# Relay_Board_V5.net
KiCad netlist of a schematic drawn in EAGLE
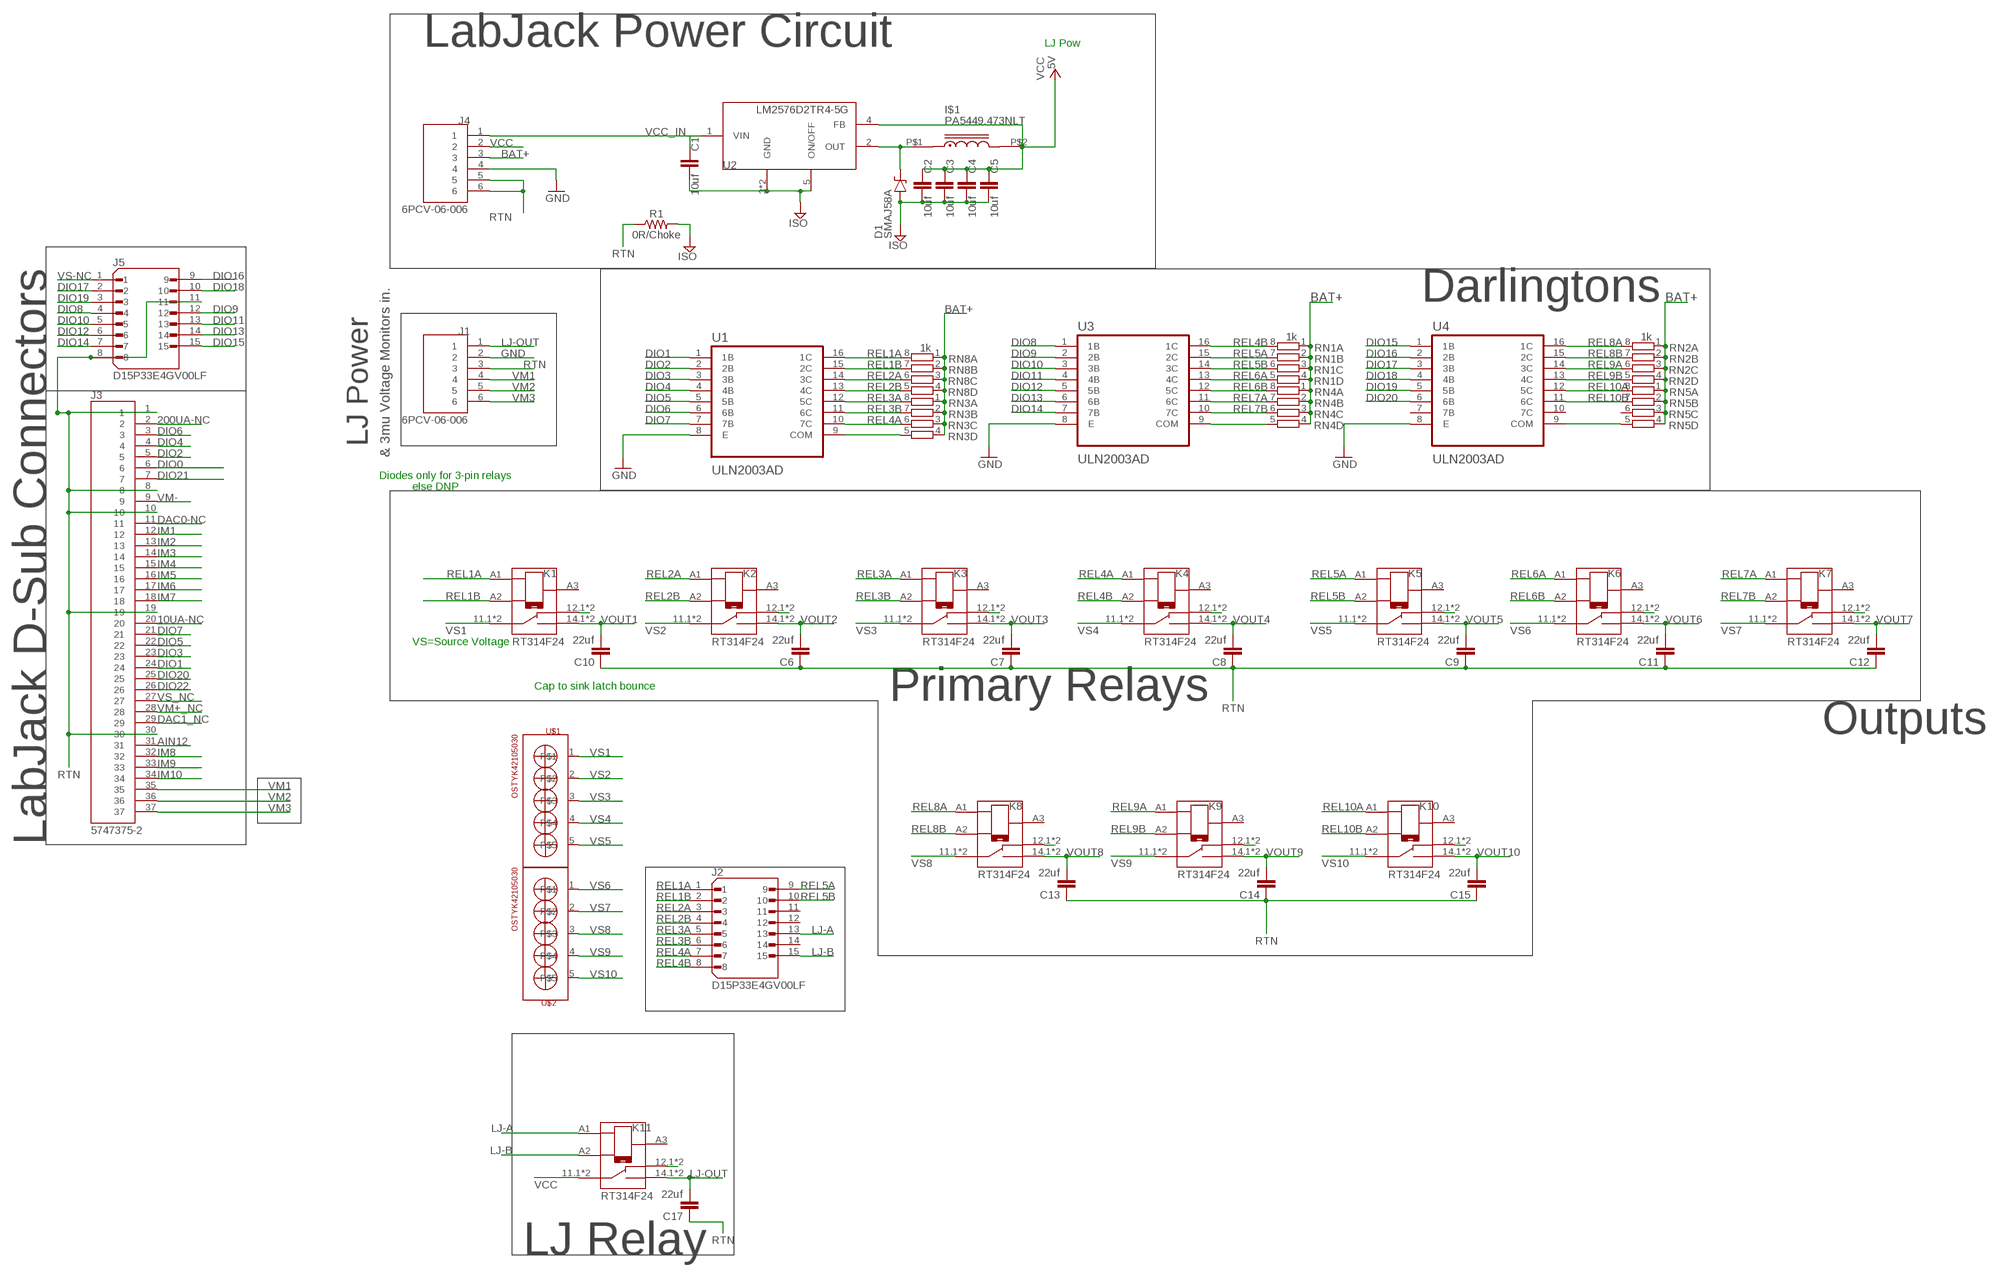
[diagram p0: schematic, sheet 1, part 1 of 2]
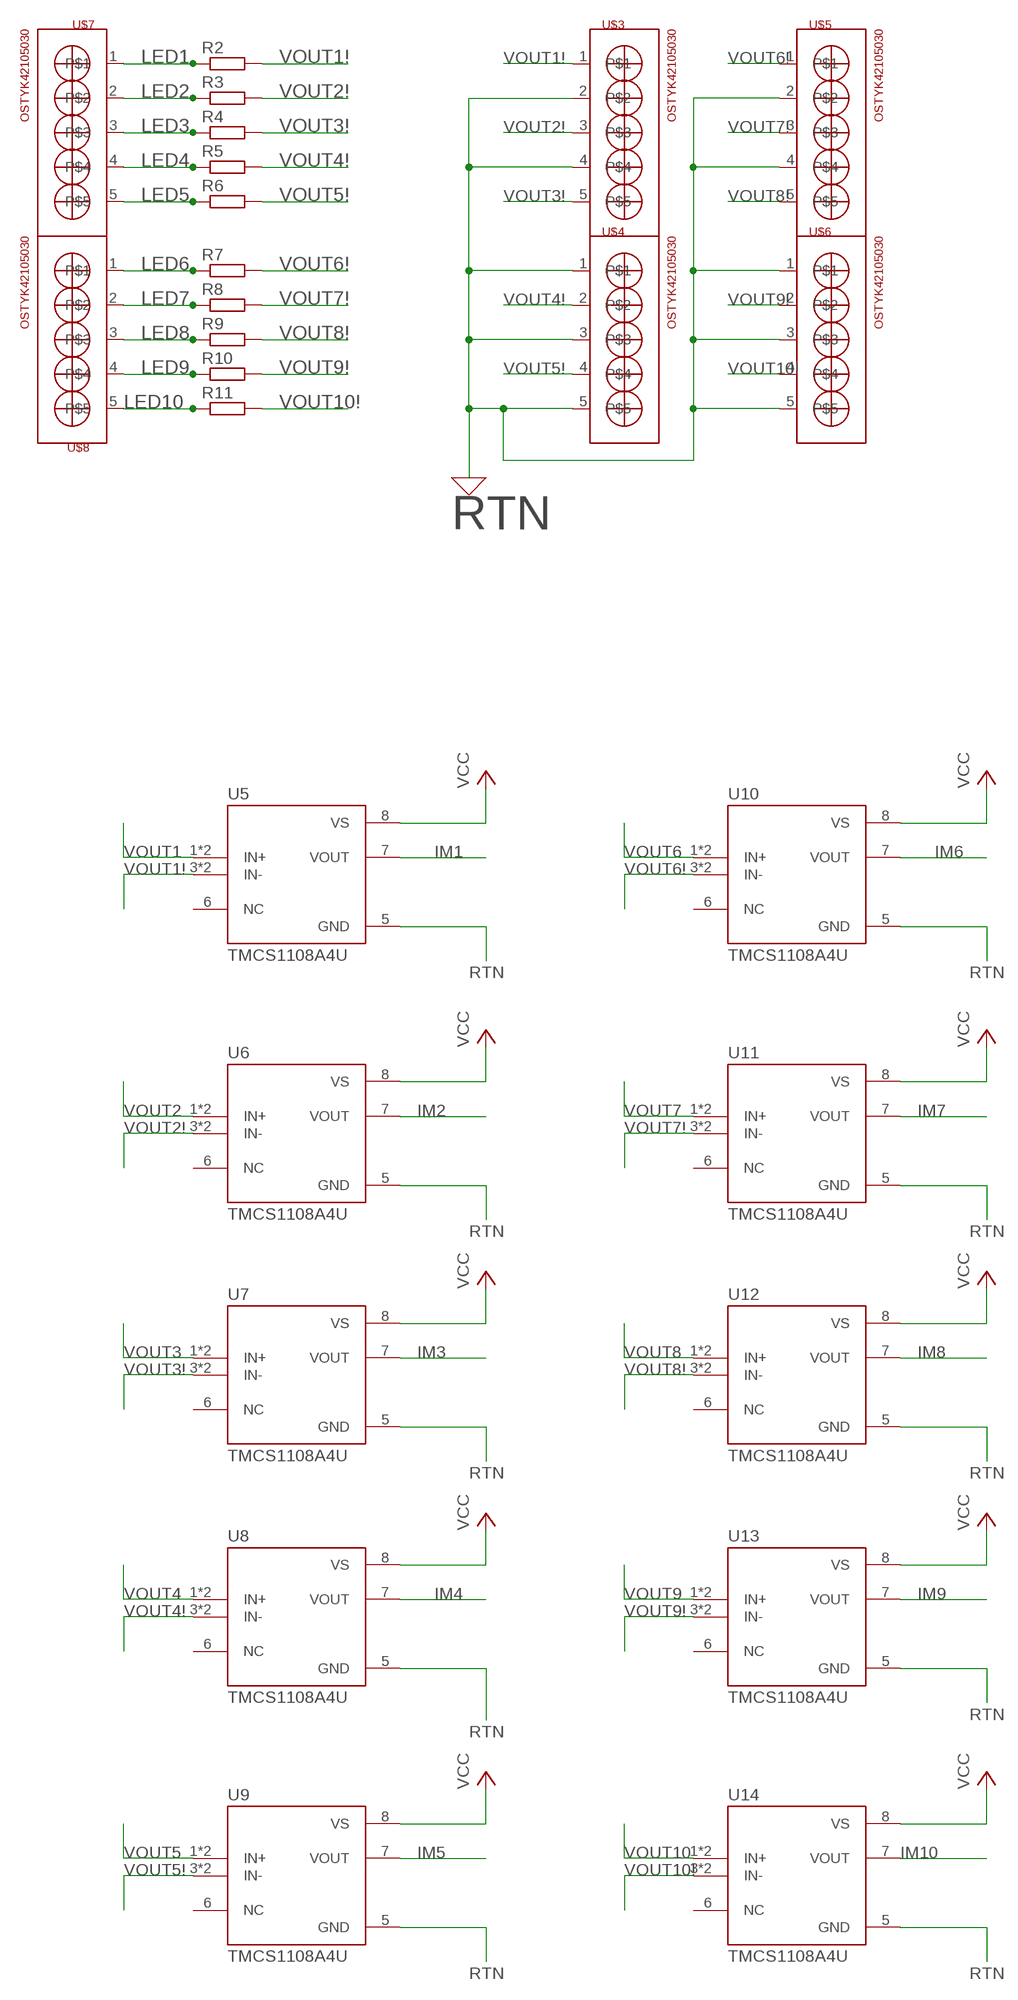
[diagram p1: schematic, sheet 1, part 2 of 2]

(export (version "E")
  (design (tool "Eeschema 10.0.6"))
  (components
    (comp (ref "C1")
      (value "10uf")
      (footprint "eagle-import:0805")
      (libsource (lib "eagle-import") (part "39NF-0805-50V-10%"))
    )
    (comp (ref "C2")
      (value "10uf")
      (footprint "eagle-import:0805")
      (libsource (lib "eagle-import") (part "39NF-0805-50V-10%"))
    )
    (comp (ref "C3")
      (value "10uf")
      (footprint "eagle-import:0805")
      (libsource (lib "eagle-import") (part "39NF-0805-50V-10%"))
    )
    (comp (ref "C4")
      (value "10uf")
      (footprint "eagle-import:0805")
      (libsource (lib "eagle-import") (part "39NF-0805-50V-10%"))
    )
    (comp (ref "C5")
      (value "10uf")
      (footprint "eagle-import:0805")
      (libsource (lib "eagle-import") (part "39NF-0805-50V-10%"))
    )
    (comp (ref "C6")
      (value "22uf")
      (footprint "eagle-import:0603")
      (libsource (lib "eagle-import") (part "5.6NF/5600PF_0603_50V_5%"))
    )
    (comp (ref "C7")
      (value "22uf")
      (footprint "eagle-import:0603")
      (libsource (lib "eagle-import") (part "5.6NF/5600PF_0603_50V_5%"))
    )
    (comp (ref "C8")
      (value "22uf")
      (footprint "eagle-import:0603")
      (libsource (lib "eagle-import") (part "5.6NF/5600PF_0603_50V_5%"))
    )
    (comp (ref "C9")
      (value "22uf")
      (footprint "eagle-import:0603")
      (libsource (lib "eagle-import") (part "5.6NF/5600PF_0603_50V_5%"))
    )
    (comp (ref "C10")
      (value "22uf")
      (footprint "eagle-import:0603")
      (libsource (lib "eagle-import") (part "5.6NF/5600PF_0603_50V_5%"))
    )
    (comp (ref "C11")
      (value "22uf")
      (footprint "eagle-import:0603")
      (libsource (lib "eagle-import") (part "5.6NF/5600PF_0603_50V_5%"))
    )
    (comp (ref "C12")
      (value "22uf")
      (footprint "eagle-import:0603")
      (libsource (lib "eagle-import") (part "5.6NF/5600PF_0603_50V_5%"))
    )
    (comp (ref "C13")
      (value "22uf")
      (footprint "eagle-import:0603")
      (libsource (lib "eagle-import") (part "5.6NF/5600PF_0603_50V_5%"))
    )
    (comp (ref "C14")
      (value "22uf")
      (footprint "eagle-import:0603")
      (libsource (lib "eagle-import") (part "5.6NF/5600PF_0603_50V_5%"))
    )
    (comp (ref "C15")
      (value "22uf")
      (footprint "eagle-import:0603")
      (libsource (lib "eagle-import") (part "5.6NF/5600PF_0603_50V_5%"))
    )
    (comp (ref "C17")
      (value "22uf")
      (footprint "eagle-import:0603")
      (libsource (lib "eagle-import") (part "5.6NF/5600PF_0603_50V_5%"))
    )
    (comp (ref "D1")
      (value "SMAJ58A")
      (footprint "eagle-import:SMA")
      (fields (field (name "MF") "Littelfuse Inc."))
      (libsource (lib "eagle-import") (part "SMAJ58A"))
    )
    (comp (ref "I$1")
      (value "PA5449.473NLT")
      (footprint "eagle-import:IND_TYS4020470M-10")
      (libsource (lib "eagle-import") (part "PULSE_ELECTRONICS_INDUCTOR"))
    )
    (comp (ref "J1")
      (value "6PCV-06-006")
      (footprint "eagle-import:TE_9-1437652-5")
      (fields (field (name "COMMENT") "9-1437652-5") (field (name "MF") "TE Connectivity"))
      (libsource (lib "eagle-import") (part "6PCV-06-006"))
    )
    (comp (ref "J2")
      (value "D15P33E4GV00LF")
      (footprint "eagle-import:AMPHENOL_D15P33E4GV00LF")
      (fields (field (name "MF") "Amphenol ICC"))
      (libsource (lib "eagle-import") (part "D15P33E4GV00LF"))
    )
    (comp (ref "J3")
      (value "5747375-2")
      (footprint "eagle-import:TE_5747375-2")
      (fields (field (name "DIGI-KEY_PART_NUMBER") "A34071-ND") (field (name "MF") "TE Connectivity"))
      (libsource (lib "eagle-import") (part "5747375-2"))
    )
    (comp (ref "J4")
      (value "6PCV-06-006")
      (footprint "eagle-import:TE_9-1437652-5")
      (fields (field (name "COMMENT") "9-1437652-5") (field (name "MF") "TE Connectivity"))
      (libsource (lib "eagle-import") (part "6PCV-06-006"))
    )
    (comp (ref "J5")
      (value "D15P33E4GV00LF")
      (footprint "eagle-import:AMPHENOL_D15P33E4GV00LF")
      (fields (field (name "MF") "Amphenol ICC"))
      (libsource (lib "eagle-import") (part "D15P33E4GV00LF"))
    )
    (comp (ref "K1")
      (value "RT314F24")
      (footprint "eagle-import:TE_8-1393239-8")
      (fields (field (name "COMMENT") "8-1393239-8") (field (name "MF") "TE Connectivity"))
      (libsource (lib "eagle-import") (part "8-1393239-8"))
    )
    (comp (ref "K2")
      (value "RT314F24")
      (footprint "eagle-import:TE_8-1393239-8")
      (fields (field (name "COMMENT") "8-1393239-8") (field (name "MF") "TE Connectivity"))
      (libsource (lib "eagle-import") (part "8-1393239-8"))
    )
    (comp (ref "K3")
      (value "RT314F24")
      (footprint "eagle-import:TE_8-1393239-8")
      (fields (field (name "COMMENT") "8-1393239-8") (field (name "MF") "TE Connectivity"))
      (libsource (lib "eagle-import") (part "8-1393239-8"))
    )
    (comp (ref "K4")
      (value "RT314F24")
      (footprint "eagle-import:TE_8-1393239-8")
      (fields (field (name "COMMENT") "8-1393239-8") (field (name "MF") "TE Connectivity"))
      (libsource (lib "eagle-import") (part "8-1393239-8"))
    )
    (comp (ref "K5")
      (value "RT314F24")
      (footprint "eagle-import:TE_8-1393239-8")
      (fields (field (name "COMMENT") "8-1393239-8") (field (name "MF") "TE Connectivity"))
      (libsource (lib "eagle-import") (part "8-1393239-8"))
    )
    (comp (ref "K6")
      (value "RT314F24")
      (footprint "eagle-import:TE_8-1393239-8")
      (fields (field (name "COMMENT") "8-1393239-8") (field (name "MF") "TE Connectivity"))
      (libsource (lib "eagle-import") (part "8-1393239-8"))
    )
    (comp (ref "K7")
      (value "RT314F24")
      (footprint "eagle-import:TE_8-1393239-8")
      (fields (field (name "COMMENT") "8-1393239-8") (field (name "MF") "TE Connectivity"))
      (libsource (lib "eagle-import") (part "8-1393239-8"))
    )
    (comp (ref "K8")
      (value "RT314F24")
      (footprint "eagle-import:TE_8-1393239-8")
      (fields (field (name "COMMENT") "8-1393239-8") (field (name "MF") "TE Connectivity"))
      (libsource (lib "eagle-import") (part "8-1393239-8"))
    )
    (comp (ref "K9")
      (value "RT314F24")
      (footprint "eagle-import:TE_8-1393239-8")
      (fields (field (name "COMMENT") "8-1393239-8") (field (name "MF") "TE Connectivity"))
      (libsource (lib "eagle-import") (part "8-1393239-8"))
    )
    (comp (ref "K10")
      (value "RT314F24")
      (footprint "eagle-import:TE_8-1393239-8")
      (fields (field (name "COMMENT") "8-1393239-8") (field (name "MF") "TE Connectivity"))
      (libsource (lib "eagle-import") (part "8-1393239-8"))
    )
    (comp (ref "K11")
      (value "RT314F24")
      (footprint "eagle-import:TE_8-1393239-8")
      (fields (field (name "COMMENT") "8-1393239-8") (field (name "MF") "TE Connectivity"))
      (libsource (lib "eagle-import") (part "8-1393239-8"))
    )
    (comp (ref "R1")
      (value "0R/Choke")
      (footprint "eagle-import:0603")
      (libsource (lib "eagle-import") (part "1.8MOHM"))
    )
    (comp (ref "R2")
      (value "R-EU_0204/7")
      (footprint "eagle-import:0204_7")
      (libsource (lib "eagle-import") (part "R-EU_0204/7"))
    )
    (comp (ref "R3")
      (value "R-EU_0204/7")
      (footprint "eagle-import:0204_7")
      (libsource (lib "eagle-import") (part "R-EU_0204/7"))
    )
    (comp (ref "R4")
      (value "R-EU_0204/7")
      (footprint "eagle-import:0204_7")
      (libsource (lib "eagle-import") (part "R-EU_0204/7"))
    )
    (comp (ref "R5")
      (value "R-EU_0204/7")
      (footprint "eagle-import:0204_7")
      (libsource (lib "eagle-import") (part "R-EU_0204/7"))
    )
    (comp (ref "R6")
      (value "R-EU_0204/7")
      (footprint "eagle-import:0204_7")
      (libsource (lib "eagle-import") (part "R-EU_0204/7"))
    )
    (comp (ref "R7")
      (value "R-EU_0204/7")
      (footprint "eagle-import:0204_7")
      (libsource (lib "eagle-import") (part "R-EU_0204/7"))
    )
    (comp (ref "R8")
      (value "R-EU_0204/7")
      (footprint "eagle-import:0204_7")
      (libsource (lib "eagle-import") (part "R-EU_0204/7"))
    )
    (comp (ref "R9")
      (value "R-EU_0204/7")
      (footprint "eagle-import:0204_7")
      (libsource (lib "eagle-import") (part "R-EU_0204/7"))
    )
    (comp (ref "R10")
      (value "R-EU_0204/7")
      (footprint "eagle-import:0204_7")
      (libsource (lib "eagle-import") (part "R-EU_0204/7"))
    )
    (comp (ref "R11")
      (value "R-EU_0204/7")
      (footprint "eagle-import:0204_7")
      (libsource (lib "eagle-import") (part "R-EU_0204/7"))
    )
    (comp (ref "RN1")
      (value "1k")
      (footprint "eagle-import:CAY16")
      (fields (field (name "PART_NUMBER") "064R_10K_/_CAY16-103J4LF"))
      (libsource (lib "eagle-import") (part "0016_064R_10K_/_CAY16-103J4LF"))
    )
    (comp (ref "RN2")
      (value "1k")
      (footprint "eagle-import:CAY16")
      (fields (field (name "PART_NUMBER") "064R_10K_/_CAY16-103J4LF"))
      (libsource (lib "eagle-import") (part "0016_064R_10K_/_CAY16-103J4LF"))
    )
    (comp (ref "RN3")
      (value "1k")
      (footprint "eagle-import:CAY16")
      (fields (field (name "PART_NUMBER") "064R_10K_/_CAY16-103J4LF"))
      (libsource (lib "eagle-import") (part "0016_064R_10K_/_CAY16-103J4LF"))
    )
    (comp (ref "RN4")
      (value "1k")
      (footprint "eagle-import:CAY16")
      (fields (field (name "PART_NUMBER") "064R_10K_/_CAY16-103J4LF"))
      (libsource (lib "eagle-import") (part "0016_064R_10K_/_CAY16-103J4LF"))
    )
    (comp (ref "RN5")
      (value "1k")
      (footprint "eagle-import:CAY16")
      (fields (field (name "PART_NUMBER") "064R_10K_/_CAY16-103J4LF"))
      (libsource (lib "eagle-import") (part "0016_064R_10K_/_CAY16-103J4LF"))
    )
    (comp (ref "RN8")
      (value "1k")
      (footprint "eagle-import:CAY16")
      (fields (field (name "PART_NUMBER") "064R_10K_/_CAY16-103J4LF"))
      (libsource (lib "eagle-import") (part "0016_064R_10K_/_CAY16-103J4LF"))
    )
    (comp (ref "U$1")
      (value "OSTYK42105030")
      (footprint "eagle-import:OSTYK42105030")
      (fields (field (name "MF") "On Shore Technology Inc."))
      (libsource (lib "eagle-import") (part "OSTYK42105030"))
    )
    (comp (ref "U$2")
      (value "OSTYK42105030")
      (footprint "eagle-import:OSTYK42105030")
      (fields (field (name "MF") "On Shore Technology Inc."))
      (libsource (lib "eagle-import") (part "OSTYK42105030"))
    )
    (comp (ref "U$3")
      (value "OSTYK42105030")
      (footprint "eagle-import:OSTYK42105030")
      (fields (field (name "MF") "On Shore Technology Inc."))
      (libsource (lib "eagle-import") (part "OSTYK42105030"))
    )
    (comp (ref "U$4")
      (value "OSTYK42105030")
      (footprint "eagle-import:OSTYK42105030")
      (fields (field (name "MF") "On Shore Technology Inc."))
      (libsource (lib "eagle-import") (part "OSTYK42105030"))
    )
    (comp (ref "U$5")
      (value "OSTYK42105030")
      (footprint "eagle-import:OSTYK42105030")
      (fields (field (name "MF") "On Shore Technology Inc."))
      (libsource (lib "eagle-import") (part "OSTYK42105030"))
    )
    (comp (ref "U$6")
      (value "OSTYK42105030")
      (footprint "eagle-import:OSTYK42105030")
      (fields (field (name "MF") "On Shore Technology Inc."))
      (libsource (lib "eagle-import") (part "OSTYK42105030"))
    )
    (comp (ref "U$7")
      (value "OSTYK42105030")
      (footprint "eagle-import:OSTYK42105030")
      (fields (field (name "MF") "On Shore Technology Inc."))
      (libsource (lib "eagle-import") (part "OSTYK42105030"))
    )
    (comp (ref "U$8")
      (value "OSTYK42105030")
      (footprint "eagle-import:OSTYK42105030")
      (fields (field (name "MF") "On Shore Technology Inc."))
      (libsource (lib "eagle-import") (part "OSTYK42105030"))
    )
    (comp (ref "U1")
      (value "ULN2003AD")
      (footprint "eagle-import:SOIC127P600X175-16N")
      (fields (field (name "MF") "Texas Instruments"))
      (libsource (lib "eagle-import") (part "ULN2003AD"))
    )
    (comp (ref "U2")
      (value "LM2576D2TR4-5G")
      (footprint "eagle-import:D2PAK-5")
      (fields (field (name "MF") "ON Semiconductor"))
      (libsource (lib "eagle-import") (part "LM2576D2TR4-5G"))
    )
    (comp (ref "U3")
      (value "ULN2003AD")
      (footprint "eagle-import:SOIC127P600X175-16N")
      (fields (field (name "MF") "Texas Instruments"))
      (libsource (lib "eagle-import") (part "ULN2003AD"))
    )
    (comp (ref "U4")
      (value "ULN2003AD")
      (footprint "eagle-import:SOIC127P600X175-16N")
      (fields (field (name "MF") "Texas Instruments"))
      (libsource (lib "eagle-import") (part "ULN2003AD"))
    )
    (comp (ref "U5")
      (value "TMCS1108A4U")
      (footprint "eagle-import:SOIC127P599X175-8N")
      (fields (field (name "MF") "Texas Instruments") (field (name "MP") "TMCS1108A3UQDRQ1"))
      (libsource (lib "eagle-import") (part "TMCS1108A3UQDRQ1"))
    )
    (comp (ref "U6")
      (value "TMCS1108A4U")
      (footprint "eagle-import:SOIC127P599X175-8N")
      (fields (field (name "MF") "Texas Instruments") (field (name "MP") "TMCS1108A3UQDRQ1"))
      (libsource (lib "eagle-import") (part "TMCS1108A3UQDRQ1"))
    )
    (comp (ref "U7")
      (value "TMCS1108A4U")
      (footprint "eagle-import:SOIC127P599X175-8N")
      (fields (field (name "MF") "Texas Instruments") (field (name "MP") "TMCS1108A3UQDRQ1"))
      (libsource (lib "eagle-import") (part "TMCS1108A3UQDRQ1"))
    )
    (comp (ref "U8")
      (value "TMCS1108A4U")
      (footprint "eagle-import:SOIC127P599X175-8N")
      (fields (field (name "MF") "Texas Instruments") (field (name "MP") "TMCS1108A3UQDRQ1"))
      (libsource (lib "eagle-import") (part "TMCS1108A3UQDRQ1"))
    )
    (comp (ref "U9")
      (value "TMCS1108A4U")
      (footprint "eagle-import:SOIC127P599X175-8N")
      (fields (field (name "MF") "Texas Instruments") (field (name "MP") "TMCS1108A3UQDRQ1"))
      (libsource (lib "eagle-import") (part "TMCS1108A3UQDRQ1"))
    )
    (comp (ref "U10")
      (value "TMCS1108A4U")
      (footprint "eagle-import:SOIC127P599X175-8N")
      (fields (field (name "MF") "Texas Instruments") (field (name "MP") "TMCS1108A3UQDRQ1"))
      (libsource (lib "eagle-import") (part "TMCS1108A3UQDRQ1"))
    )
    (comp (ref "U11")
      (value "TMCS1108A4U")
      (footprint "eagle-import:SOIC127P599X175-8N")
      (fields (field (name "MF") "Texas Instruments") (field (name "MP") "TMCS1108A3UQDRQ1"))
      (libsource (lib "eagle-import") (part "TMCS1108A3UQDRQ1"))
    )
    (comp (ref "U12")
      (value "TMCS1108A4U")
      (footprint "eagle-import:SOIC127P599X175-8N")
      (fields (field (name "MF") "Texas Instruments") (field (name "MP") "TMCS1108A3UQDRQ1"))
      (libsource (lib "eagle-import") (part "TMCS1108A3UQDRQ1"))
    )
    (comp (ref "U13")
      (value "TMCS1108A4U")
      (footprint "eagle-import:SOIC127P599X175-8N")
      (fields (field (name "MF") "Texas Instruments") (field (name "MP") "TMCS1108A3UQDRQ1"))
      (libsource (lib "eagle-import") (part "TMCS1108A3UQDRQ1"))
    )
    (comp (ref "U14")
      (value "TMCS1108A4U")
      (footprint "eagle-import:SOIC127P599X175-8N")
      (fields (field (name "MF") "Texas Instruments") (field (name "MP") "TMCS1108A3UQDRQ1"))
      (libsource (lib "eagle-import") (part "TMCS1108A3UQDRQ1"))
    )
  )
  (nets
    (net (code "1") (name "/10UA-NC") (class "Default")
      (node (ref "J3") (pin "20") (pinfunction "20_20") (pintype "passive"))
    )
    (net (code "2") (name "/200UA-NC") (class "Default")
      (node (ref "J3") (pin "2") (pinfunction "2_2") (pintype "passive"))
    )
    (net (code "3") (name "/AIN12") (class "Default")
      (node (ref "J3") (pin "31") (pinfunction "31_31") (pintype "passive"))
    )
    (net (code "4") (name "/BAT+") (class "Default")
      (node (ref "J4") (pin "3") (pinfunction "3_3") (pintype "passive"))
      (node (ref "RN1") (pin "1") (pinfunction "1_1") (pintype "passive"))
      (node (ref "RN1") (pin "2") (pinfunction "1_2") (pintype "passive"))
      (node (ref "RN1") (pin "3") (pinfunction "1_3") (pintype "passive"))
      (node (ref "RN1") (pin "4") (pinfunction "1_4") (pintype "passive"))
      (node (ref "RN2") (pin "1") (pinfunction "1_1") (pintype "passive"))
      (node (ref "RN2") (pin "2") (pinfunction "1_2") (pintype "passive"))
      (node (ref "RN2") (pin "3") (pinfunction "1_3") (pintype "passive"))
      (node (ref "RN2") (pin "4") (pinfunction "1_4") (pintype "passive"))
      (node (ref "RN3") (pin "1") (pinfunction "1_1") (pintype "passive"))
      (node (ref "RN3") (pin "2") (pinfunction "1_2") (pintype "passive"))
      (node (ref "RN3") (pin "3") (pinfunction "1_3") (pintype "passive"))
      (node (ref "RN3") (pin "4") (pinfunction "1_4") (pintype "passive"))
      (node (ref "RN4") (pin "1") (pinfunction "1_1") (pintype "passive"))
      (node (ref "RN4") (pin "2") (pinfunction "1_2") (pintype "passive"))
      (node (ref "RN4") (pin "3") (pinfunction "1_3") (pintype "passive"))
      (node (ref "RN4") (pin "4") (pinfunction "1_4") (pintype "passive"))
      (node (ref "RN5") (pin "1") (pinfunction "1_1") (pintype "passive"))
      (node (ref "RN5") (pin "2") (pinfunction "1_2") (pintype "passive"))
      (node (ref "RN5") (pin "3") (pinfunction "1_3") (pintype "passive"))
      (node (ref "RN5") (pin "4") (pinfunction "1_4") (pintype "passive"))
      (node (ref "RN8") (pin "1") (pinfunction "1_1") (pintype "passive"))
      (node (ref "RN8") (pin "2") (pinfunction "1_2") (pintype "passive"))
      (node (ref "RN8") (pin "3") (pinfunction "1_3") (pintype "passive"))
      (node (ref "RN8") (pin "4") (pinfunction "1_4") (pintype "passive"))
    )
    (net (code "5") (name "/DAC0-NC") (class "Default")
      (node (ref "J3") (pin "11") (pinfunction "11_11") (pintype "passive"))
    )
    (net (code "6") (name "/DAC1_NC") (class "Default")
      (node (ref "J3") (pin "29") (pinfunction "29_29") (pintype "passive"))
    )
    (net (code "7") (name "/DIO0") (class "Default")
      (node (ref "J3") (pin "6") (pinfunction "6_6") (pintype "passive"))
    )
    (net (code "8") (name "/DIO1") (class "Default")
      (node (ref "J3") (pin "24") (pinfunction "24_24") (pintype "passive"))
      (node (ref "U1") (pin "1") (pinfunction "1B_1") (pintype "input"))
    )
    (net (code "9") (name "/DIO2") (class "Default")
      (node (ref "J3") (pin "5") (pinfunction "5_5") (pintype "passive"))
      (node (ref "U1") (pin "2") (pinfunction "2B_2") (pintype "input"))
    )
    (net (code "10") (name "/DIO3") (class "Default")
      (node (ref "J3") (pin "23") (pinfunction "23_23") (pintype "passive"))
      (node (ref "U1") (pin "3") (pinfunction "3B_3") (pintype "input"))
    )
    (net (code "11") (name "/DIO4") (class "Default")
      (node (ref "J3") (pin "4") (pinfunction "4_4") (pintype "passive"))
      (node (ref "U1") (pin "4") (pinfunction "4B_4") (pintype "input"))
    )
    (net (code "12") (name "/DIO5") (class "Default")
      (node (ref "J3") (pin "22") (pinfunction "22_22") (pintype "passive"))
      (node (ref "U1") (pin "5") (pinfunction "5B_5") (pintype "input"))
    )
    (net (code "13") (name "/DIO6") (class "Default")
      (node (ref "J3") (pin "3") (pinfunction "3_3") (pintype "passive"))
      (node (ref "U1") (pin "6") (pinfunction "6B_6") (pintype "input"))
    )
    (net (code "14") (name "/DIO7") (class "Default")
      (node (ref "J3") (pin "21") (pinfunction "21_21") (pintype "passive"))
      (node (ref "U1") (pin "7") (pinfunction "7B_7") (pintype "input"))
    )
    (net (code "15") (name "/DIO8") (class "Default")
      (node (ref "J5") (pin "4") (pinfunction "4_4") (pintype "passive"))
      (node (ref "U3") (pin "1") (pinfunction "1B_1") (pintype "input"))
    )
    (net (code "16") (name "/DIO9") (class "Default")
      (node (ref "J5") (pin "12") (pinfunction "12_12") (pintype "passive"))
      (node (ref "U3") (pin "2") (pinfunction "2B_2") (pintype "input"))
    )
    (net (code "17") (name "/DIO10") (class "Default")
      (node (ref "J5") (pin "5") (pinfunction "5_5") (pintype "passive"))
      (node (ref "U3") (pin "3") (pinfunction "3B_3") (pintype "input"))
    )
    (net (code "18") (name "/DIO11") (class "Default")
      (node (ref "J5") (pin "13") (pinfunction "13_13") (pintype "passive"))
      (node (ref "U3") (pin "4") (pinfunction "4B_4") (pintype "input"))
    )
    (net (code "19") (name "/DIO12") (class "Default")
      (node (ref "J5") (pin "6") (pinfunction "6_6") (pintype "passive"))
      (node (ref "U3") (pin "5") (pinfunction "5B_5") (pintype "input"))
    )
    (net (code "20") (name "/DIO13") (class "Default")
      (node (ref "J5") (pin "14") (pinfunction "14_14") (pintype "passive"))
      (node (ref "U3") (pin "6") (pinfunction "6B_6") (pintype "input"))
    )
    (net (code "21") (name "/DIO14") (class "Default")
      (node (ref "J5") (pin "7") (pinfunction "7_7") (pintype "passive"))
      (node (ref "U3") (pin "7") (pinfunction "7B_7") (pintype "input"))
    )
    (net (code "22") (name "/DIO15") (class "Default")
      (node (ref "J5") (pin "15") (pinfunction "15_15") (pintype "passive"))
      (node (ref "U4") (pin "1") (pinfunction "1B_1") (pintype "input"))
    )
    (net (code "23") (name "/DIO16") (class "Default")
      (node (ref "J5") (pin "9") (pinfunction "9_9") (pintype "passive"))
      (node (ref "U4") (pin "2") (pinfunction "2B_2") (pintype "input"))
    )
    (net (code "24") (name "/DIO17") (class "Default")
      (node (ref "J5") (pin "2") (pinfunction "2_2") (pintype "passive"))
      (node (ref "U4") (pin "3") (pinfunction "3B_3") (pintype "input"))
    )
    (net (code "25") (name "/DIO18") (class "Default")
      (node (ref "J5") (pin "10") (pinfunction "10_10") (pintype "passive"))
      (node (ref "U4") (pin "4") (pinfunction "4B_4") (pintype "input"))
    )
    (net (code "26") (name "/DIO19") (class "Default")
      (node (ref "J5") (pin "3") (pinfunction "3_3") (pintype "passive"))
      (node (ref "U4") (pin "5") (pinfunction "5B_5") (pintype "input"))
    )
    (net (code "27") (name "/DIO20") (class "Default")
      (node (ref "J3") (pin "25") (pinfunction "25_25") (pintype "passive"))
      (node (ref "U4") (pin "6") (pinfunction "6B_6") (pintype "input"))
    )
    (net (code "28") (name "/DIO21") (class "Default")
      (node (ref "J3") (pin "7") (pinfunction "7_7") (pintype "passive"))
    )
    (net (code "29") (name "/DIO22") (class "Default")
      (node (ref "J3") (pin "26") (pinfunction "26_26") (pintype "passive"))
    )
    (net (code "30") (name "/IM1") (class "Default")
      (node (ref "J3") (pin "12") (pinfunction "12_12") (pintype "passive"))
      (node (ref "U5") (pin "7") (pinfunction "VOUT_7") (pintype "output"))
    )
    (net (code "31") (name "/IM2") (class "Default")
      (node (ref "J3") (pin "13") (pinfunction "13_13") (pintype "passive"))
      (node (ref "U6") (pin "7") (pinfunction "VOUT_7") (pintype "output"))
    )
    (net (code "32") (name "/IM3") (class "Default")
      (node (ref "J3") (pin "14") (pinfunction "14_14") (pintype "passive"))
      (node (ref "U7") (pin "7") (pinfunction "VOUT_7") (pintype "output"))
    )
    (net (code "33") (name "/IM4") (class "Default")
      (node (ref "J3") (pin "15") (pinfunction "15_15") (pintype "passive"))
      (node (ref "U8") (pin "7") (pinfunction "VOUT_7") (pintype "output"))
    )
    (net (code "34") (name "/IM5") (class "Default")
      (node (ref "J3") (pin "16") (pinfunction "16_16") (pintype "passive"))
      (node (ref "U9") (pin "7") (pinfunction "VOUT_7") (pintype "output"))
    )
    (net (code "35") (name "/IM6") (class "Default")
      (node (ref "J3") (pin "17") (pinfunction "17_17") (pintype "passive"))
      (node (ref "U10") (pin "7") (pinfunction "VOUT_7") (pintype "output"))
    )
    (net (code "36") (name "/IM7") (class "Default")
      (node (ref "J3") (pin "18") (pinfunction "18_18") (pintype "passive"))
      (node (ref "U11") (pin "7") (pinfunction "VOUT_7") (pintype "output"))
    )
    (net (code "37") (name "/IM8") (class "Default")
      (node (ref "J3") (pin "32") (pinfunction "32_32") (pintype "passive"))
      (node (ref "U12") (pin "7") (pinfunction "VOUT_7") (pintype "output"))
    )
    (net (code "38") (name "/IM9") (class "Default")
      (node (ref "J3") (pin "33") (pinfunction "33_33") (pintype "passive"))
      (node (ref "U13") (pin "7") (pinfunction "VOUT_7") (pintype "output"))
    )
    (net (code "39") (name "/IM10") (class "Default")
      (node (ref "J3") (pin "34") (pinfunction "34_34") (pintype "passive"))
      (node (ref "U14") (pin "7") (pinfunction "VOUT_7") (pintype "output"))
    )
    (net (code "40") (name "/LED1") (class "Default")
      (node (ref "R2") (pin "1") (pinfunction "1_1") (pintype "passive"))
      (node (ref "U$7") (pin "1") (pinfunction "P$1_1") (pintype "bidirectional"))
    )
    (net (code "41") (name "/LED2") (class "Default")
      (node (ref "R3") (pin "1") (pinfunction "1_1") (pintype "passive"))
      (node (ref "U$7") (pin "2") (pinfunction "P$2_2") (pintype "bidirectional"))
    )
    (net (code "42") (name "/LED3") (class "Default")
      (node (ref "R4") (pin "1") (pinfunction "1_1") (pintype "passive"))
      (node (ref "U$7") (pin "3") (pinfunction "P$3_3") (pintype "bidirectional"))
    )
    (net (code "43") (name "/LED4") (class "Default")
      (node (ref "R5") (pin "1") (pinfunction "1_1") (pintype "passive"))
      (node (ref "U$7") (pin "4") (pinfunction "P$4_4") (pintype "bidirectional"))
    )
    (net (code "44") (name "/LED5") (class "Default")
      (node (ref "R6") (pin "1") (pinfunction "1_1") (pintype "passive"))
      (node (ref "U$7") (pin "5") (pinfunction "P$5_5") (pintype "bidirectional"))
    )
    (net (code "45") (name "/LED6") (class "Default")
      (node (ref "R7") (pin "1") (pinfunction "1_1") (pintype "passive"))
      (node (ref "U$8") (pin "1") (pinfunction "P$1_1") (pintype "bidirectional"))
    )
    (net (code "46") (name "/LED7") (class "Default")
      (node (ref "R8") (pin "1") (pinfunction "1_1") (pintype "passive"))
      (node (ref "U$8") (pin "2") (pinfunction "P$2_2") (pintype "bidirectional"))
    )
    (net (code "47") (name "/LED8") (class "Default")
      (node (ref "R9") (pin "1") (pinfunction "1_1") (pintype "passive"))
      (node (ref "U$8") (pin "3") (pinfunction "P$3_3") (pintype "bidirectional"))
    )
    (net (code "48") (name "/LED9") (class "Default")
      (node (ref "R10") (pin "1") (pinfunction "1_1") (pintype "passive"))
      (node (ref "U$8") (pin "4") (pinfunction "P$4_4") (pintype "bidirectional"))
    )
    (net (code "49") (name "/LED10") (class "Default")
      (node (ref "R11") (pin "1") (pinfunction "1_1") (pintype "passive"))
      (node (ref "U$8") (pin "5") (pinfunction "P$5_5") (pintype "bidirectional"))
    )
    (net (code "50") (name "/LJ-A") (class "Default")
      (node (ref "J2") (pin "13") (pinfunction "13_13") (pintype "passive"))
      (node (ref "K11") (pin "A1") (pinfunction "A1_A1") (pintype "passive"))
    )
    (net (code "51") (name "/LJ-B") (class "Default")
      (node (ref "J2") (pin "15") (pinfunction "15_15") (pintype "passive"))
      (node (ref "K11") (pin "A2") (pinfunction "A2_A2") (pintype "passive"))
    )
    (net (code "52") (name "/LJ-OUT") (class "Default")
      (node (ref "C17") (pin "2") (pinfunction "2_2") (pintype "passive"))
      (node (ref "J1") (pin "1") (pinfunction "1_1") (pintype "passive"))
      (node (ref "K11") (pin "14.1") (pinfunction "14_14.1") (pintype "passive"))
      (node (ref "K11") (pin "14.2") (pinfunction "14_14.2") (pintype "passive"))
    )
    (net (code "53") (name "/REL1A") (class "Default")
      (node (ref "J2") (pin "1") (pinfunction "1_1") (pintype "passive"))
      (node (ref "K1") (pin "A1") (pinfunction "A1_A1") (pintype "passive"))
      (node (ref "RN8") (pin "8") (pinfunction "2_8") (pintype "passive"))
      (node (ref "U1") (pin "16") (pinfunction "1C_16") (pintype "output"))
    )
    (net (code "54") (name "/REL1B") (class "Default")
      (node (ref "J2") (pin "2") (pinfunction "2_2") (pintype "passive"))
      (node (ref "K1") (pin "A2") (pinfunction "A2_A2") (pintype "passive"))
      (node (ref "RN8") (pin "7") (pinfunction "2_7") (pintype "passive"))
      (node (ref "U1") (pin "15") (pinfunction "2C_15") (pintype "output"))
    )
    (net (code "55") (name "/REL2A") (class "Default")
      (node (ref "J2") (pin "3") (pinfunction "3_3") (pintype "passive"))
      (node (ref "K2") (pin "A1") (pinfunction "A1_A1") (pintype "passive"))
      (node (ref "RN8") (pin "6") (pinfunction "2_6") (pintype "passive"))
      (node (ref "U1") (pin "14") (pinfunction "3C_14") (pintype "output"))
    )
    (net (code "56") (name "/REL2B") (class "Default")
      (node (ref "J2") (pin "4") (pinfunction "4_4") (pintype "passive"))
      (node (ref "K2") (pin "A2") (pinfunction "A2_A2") (pintype "passive"))
      (node (ref "RN8") (pin "5") (pinfunction "2_5") (pintype "passive"))
      (node (ref "U1") (pin "13") (pinfunction "4C_13") (pintype "output"))
    )
    (net (code "57") (name "/REL3A") (class "Default")
      (node (ref "J2") (pin "5") (pinfunction "5_5") (pintype "passive"))
      (node (ref "K3") (pin "A1") (pinfunction "A1_A1") (pintype "passive"))
      (node (ref "RN3") (pin "8") (pinfunction "2_8") (pintype "passive"))
      (node (ref "U1") (pin "12") (pinfunction "5C_12") (pintype "output"))
    )
    (net (code "58") (name "/REL3B") (class "Default")
      (node (ref "J2") (pin "6") (pinfunction "6_6") (pintype "passive"))
      (node (ref "K3") (pin "A2") (pinfunction "A2_A2") (pintype "passive"))
      (node (ref "RN3") (pin "7") (pinfunction "2_7") (pintype "passive"))
      (node (ref "U1") (pin "11") (pinfunction "6C_11") (pintype "output"))
    )
    (net (code "59") (name "/REL4A") (class "Default")
      (node (ref "J2") (pin "7") (pinfunction "7_7") (pintype "passive"))
      (node (ref "K4") (pin "A1") (pinfunction "A1_A1") (pintype "passive"))
      (node (ref "RN3") (pin "6") (pinfunction "2_6") (pintype "passive"))
      (node (ref "U1") (pin "10") (pinfunction "7C_10") (pintype "output"))
    )
    (net (code "60") (name "/REL4B") (class "Default")
      (node (ref "J2") (pin "8") (pinfunction "8_8") (pintype "passive"))
      (node (ref "K4") (pin "A2") (pinfunction "A2_A2") (pintype "passive"))
      (node (ref "RN1") (pin "8") (pinfunction "2_8") (pintype "passive"))
      (node (ref "U3") (pin "16") (pinfunction "1C_16") (pintype "output"))
    )
    (net (code "61") (name "/REL5A") (class "Default")
      (node (ref "J2") (pin "9") (pinfunction "9_9") (pintype "passive"))
      (node (ref "K5") (pin "A1") (pinfunction "A1_A1") (pintype "passive"))
      (node (ref "RN1") (pin "7") (pinfunction "2_7") (pintype "passive"))
      (node (ref "U3") (pin "15") (pinfunction "2C_15") (pintype "output"))
    )
    (net (code "62") (name "/REL5B") (class "Default")
      (node (ref "J2") (pin "10") (pinfunction "10_10") (pintype "passive"))
      (node (ref "K5") (pin "A2") (pinfunction "A2_A2") (pintype "passive"))
      (node (ref "RN1") (pin "6") (pinfunction "2_6") (pintype "passive"))
      (node (ref "U3") (pin "14") (pinfunction "3C_14") (pintype "output"))
    )
    (net (code "63") (name "/REL6A") (class "Default")
      (node (ref "K6") (pin "A1") (pinfunction "A1_A1") (pintype "passive"))
      (node (ref "RN1") (pin "5") (pinfunction "2_5") (pintype "passive"))
      (node (ref "U3") (pin "13") (pinfunction "4C_13") (pintype "output"))
    )
    (net (code "64") (name "/REL6B") (class "Default")
      (node (ref "K6") (pin "A2") (pinfunction "A2_A2") (pintype "passive"))
      (node (ref "RN4") (pin "8") (pinfunction "2_8") (pintype "passive"))
      (node (ref "U3") (pin "12") (pinfunction "5C_12") (pintype "output"))
    )
    (net (code "65") (name "/REL7A") (class "Default")
      (node (ref "K7") (pin "A1") (pinfunction "A1_A1") (pintype "passive"))
      (node (ref "RN4") (pin "7") (pinfunction "2_7") (pintype "passive"))
      (node (ref "U3") (pin "11") (pinfunction "6C_11") (pintype "output"))
    )
    (net (code "66") (name "/REL7B") (class "Default")
      (node (ref "K7") (pin "A2") (pinfunction "A2_A2") (pintype "passive"))
      (node (ref "RN4") (pin "6") (pinfunction "2_6") (pintype "passive"))
      (node (ref "U3") (pin "10") (pinfunction "7C_10") (pintype "output"))
    )
    (net (code "67") (name "/REL8A") (class "Default")
      (node (ref "K8") (pin "A1") (pinfunction "A1_A1") (pintype "passive"))
      (node (ref "RN2") (pin "8") (pinfunction "2_8") (pintype "passive"))
      (node (ref "U4") (pin "16") (pinfunction "1C_16") (pintype "output"))
    )
    (net (code "68") (name "/REL8B") (class "Default")
      (node (ref "K8") (pin "A2") (pinfunction "A2_A2") (pintype "passive"))
      (node (ref "RN2") (pin "7") (pinfunction "2_7") (pintype "passive"))
      (node (ref "U4") (pin "15") (pinfunction "2C_15") (pintype "output"))
    )
    (net (code "69") (name "/REL9A") (class "Default")
      (node (ref "K9") (pin "A1") (pinfunction "A1_A1") (pintype "passive"))
      (node (ref "RN2") (pin "6") (pinfunction "2_6") (pintype "passive"))
      (node (ref "U4") (pin "14") (pinfunction "3C_14") (pintype "output"))
    )
    (net (code "70") (name "/REL9B") (class "Default")
      (node (ref "K9") (pin "A2") (pinfunction "A2_A2") (pintype "passive"))
      (node (ref "RN2") (pin "5") (pinfunction "2_5") (pintype "passive"))
      (node (ref "U4") (pin "13") (pinfunction "4C_13") (pintype "output"))
    )
    (net (code "71") (name "/REL10A") (class "Default")
      (node (ref "K10") (pin "A1") (pinfunction "A1_A1") (pintype "passive"))
      (node (ref "RN5") (pin "8") (pinfunction "2_8") (pintype "passive"))
      (node (ref "U4") (pin "12") (pinfunction "5C_12") (pintype "output"))
    )
    (net (code "72") (name "/REL10B") (class "Default")
      (node (ref "K10") (pin "A2") (pinfunction "A2_A2") (pintype "passive"))
      (node (ref "RN5") (pin "7") (pinfunction "2_7") (pintype "passive"))
      (node (ref "U4") (pin "11") (pinfunction "6C_11") (pintype "output"))
    )
    (net (code "73") (name "/VCC_IN") (class "Default")
      (node (ref "J4") (pin "1") (pinfunction "1_1") (pintype "passive"))
      (node (ref "U2") (pin "1") (pinfunction "VIN_1") (pintype "input"))
    )
    (net (code "74") (name "/VM+_NC") (class "Default")
      (node (ref "J3") (pin "28") (pinfunction "28_28") (pintype "passive"))
    )
    (net (code "75") (name "/VM-") (class "Default")
      (node (ref "J3") (pin "9") (pinfunction "9_9") (pintype "passive"))
    )
    (net (code "76") (name "/VM1") (class "Default")
      (node (ref "J1") (pin "4") (pinfunction "4_4") (pintype "passive"))
      (node (ref "J3") (pin "35") (pinfunction "35_35") (pintype "passive"))
    )
    (net (code "77") (name "/VM2") (class "Default")
      (node (ref "J1") (pin "5") (pinfunction "5_5") (pintype "passive"))
      (node (ref "J3") (pin "36") (pinfunction "36_36") (pintype "passive"))
    )
    (net (code "78") (name "/VM3") (class "Default")
      (node (ref "J1") (pin "6") (pinfunction "6_6") (pintype "passive"))
      (node (ref "J3") (pin "37") (pinfunction "37_37") (pintype "passive"))
    )
    (net (code "79") (name "/VOUT1") (class "Default")
      (node (ref "C10") (pin "2") (pinfunction "2_2") (pintype "passive"))
      (node (ref "K1") (pin "14.1") (pinfunction "14_14.1") (pintype "passive"))
      (node (ref "K1") (pin "14.2") (pinfunction "14_14.2") (pintype "passive"))
      (node (ref "U5") (pin "1") (pinfunction "IN+_1") (pintype "input"))
      (node (ref "U5") (pin "2") (pinfunction "IN+_2") (pintype "input"))
    )
    (net (code "80") (name "/VOUT1~{}") (class "Default")
      (node (ref "R2") (pin "2") (pinfunction "2_2") (pintype "passive"))
      (node (ref "U$3") (pin "1") (pinfunction "P$1_1") (pintype "bidirectional"))
      (node (ref "U5") (pin "3") (pinfunction "IN-_3") (pintype "input"))
      (node (ref "U5") (pin "4") (pinfunction "IN-_4") (pintype "input"))
    )
    (net (code "81") (name "/VOUT2") (class "Default")
      (node (ref "C6") (pin "2") (pinfunction "2_2") (pintype "passive"))
      (node (ref "K2") (pin "14.1") (pinfunction "14_14.1") (pintype "passive"))
      (node (ref "K2") (pin "14.2") (pinfunction "14_14.2") (pintype "passive"))
      (node (ref "U6") (pin "1") (pinfunction "IN+_1") (pintype "input"))
      (node (ref "U6") (pin "2") (pinfunction "IN+_2") (pintype "input"))
    )
    (net (code "82") (name "/VOUT2~{}") (class "Default")
      (node (ref "R3") (pin "2") (pinfunction "2_2") (pintype "passive"))
      (node (ref "U$3") (pin "3") (pinfunction "P$3_3") (pintype "bidirectional"))
      (node (ref "U6") (pin "3") (pinfunction "IN-_3") (pintype "input"))
      (node (ref "U6") (pin "4") (pinfunction "IN-_4") (pintype "input"))
    )
    (net (code "83") (name "/VOUT3") (class "Default")
      (node (ref "C7") (pin "2") (pinfunction "2_2") (pintype "passive"))
      (node (ref "K3") (pin "14.1") (pinfunction "14_14.1") (pintype "passive"))
      (node (ref "K3") (pin "14.2") (pinfunction "14_14.2") (pintype "passive"))
      (node (ref "U7") (pin "1") (pinfunction "IN+_1") (pintype "input"))
      (node (ref "U7") (pin "2") (pinfunction "IN+_2") (pintype "input"))
    )
    (net (code "84") (name "/VOUT3~{}") (class "Default")
      (node (ref "R4") (pin "2") (pinfunction "2_2") (pintype "passive"))
      (node (ref "U$3") (pin "5") (pinfunction "P$5_5") (pintype "bidirectional"))
      (node (ref "U7") (pin "3") (pinfunction "IN-_3") (pintype "input"))
      (node (ref "U7") (pin "4") (pinfunction "IN-_4") (pintype "input"))
    )
    (net (code "85") (name "/VOUT4") (class "Default")
      (node (ref "C8") (pin "2") (pinfunction "2_2") (pintype "passive"))
      (node (ref "K4") (pin "14.1") (pinfunction "14_14.1") (pintype "passive"))
      (node (ref "K4") (pin "14.2") (pinfunction "14_14.2") (pintype "passive"))
      (node (ref "U8") (pin "1") (pinfunction "IN+_1") (pintype "input"))
      (node (ref "U8") (pin "2") (pinfunction "IN+_2") (pintype "input"))
    )
    (net (code "86") (name "/VOUT4~{}") (class "Default")
      (node (ref "R5") (pin "2") (pinfunction "2_2") (pintype "passive"))
      (node (ref "U$4") (pin "2") (pinfunction "P$2_2") (pintype "bidirectional"))
      (node (ref "U8") (pin "3") (pinfunction "IN-_3") (pintype "input"))
      (node (ref "U8") (pin "4") (pinfunction "IN-_4") (pintype "input"))
    )
    (net (code "87") (name "/VOUT5") (class "Default")
      (node (ref "C9") (pin "2") (pinfunction "2_2") (pintype "passive"))
      (node (ref "K5") (pin "14.1") (pinfunction "14_14.1") (pintype "passive"))
      (node (ref "K5") (pin "14.2") (pinfunction "14_14.2") (pintype "passive"))
      (node (ref "U9") (pin "1") (pinfunction "IN+_1") (pintype "input"))
      (node (ref "U9") (pin "2") (pinfunction "IN+_2") (pintype "input"))
    )
    (net (code "88") (name "/VOUT5~{}") (class "Default")
      (node (ref "R6") (pin "2") (pinfunction "2_2") (pintype "passive"))
      (node (ref "U$4") (pin "4") (pinfunction "P$4_4") (pintype "bidirectional"))
      (node (ref "U9") (pin "3") (pinfunction "IN-_3") (pintype "input"))
      (node (ref "U9") (pin "4") (pinfunction "IN-_4") (pintype "input"))
    )
    (net (code "89") (name "/VOUT6") (class "Default")
      (node (ref "C11") (pin "2") (pinfunction "2_2") (pintype "passive"))
      (node (ref "K6") (pin "14.1") (pinfunction "14_14.1") (pintype "passive"))
      (node (ref "K6") (pin "14.2") (pinfunction "14_14.2") (pintype "passive"))
      (node (ref "U10") (pin "1") (pinfunction "IN+_1") (pintype "input"))
      (node (ref "U10") (pin "2") (pinfunction "IN+_2") (pintype "input"))
    )
    (net (code "90") (name "/VOUT6~{}") (class "Default")
      (node (ref "R7") (pin "2") (pinfunction "2_2") (pintype "passive"))
      (node (ref "U$5") (pin "1") (pinfunction "P$1_1") (pintype "bidirectional"))
      (node (ref "U10") (pin "3") (pinfunction "IN-_3") (pintype "input"))
      (node (ref "U10") (pin "4") (pinfunction "IN-_4") (pintype "input"))
    )
    (net (code "91") (name "/VOUT7") (class "Default")
      (node (ref "C12") (pin "2") (pinfunction "2_2") (pintype "passive"))
      (node (ref "K7") (pin "14.1") (pinfunction "14_14.1") (pintype "passive"))
      (node (ref "K7") (pin "14.2") (pinfunction "14_14.2") (pintype "passive"))
      (node (ref "U11") (pin "1") (pinfunction "IN+_1") (pintype "input"))
      (node (ref "U11") (pin "2") (pinfunction "IN+_2") (pintype "input"))
    )
    (net (code "92") (name "/VOUT7~{}") (class "Default")
      (node (ref "R8") (pin "2") (pinfunction "2_2") (pintype "passive"))
      (node (ref "U$5") (pin "3") (pinfunction "P$3_3") (pintype "bidirectional"))
      (node (ref "U11") (pin "3") (pinfunction "IN-_3") (pintype "input"))
      (node (ref "U11") (pin "4") (pinfunction "IN-_4") (pintype "input"))
    )
    (net (code "93") (name "/VOUT8") (class "Default")
      (node (ref "C13") (pin "2") (pinfunction "2_2") (pintype "passive"))
      (node (ref "K8") (pin "14.1") (pinfunction "14_14.1") (pintype "passive"))
      (node (ref "K8") (pin "14.2") (pinfunction "14_14.2") (pintype "passive"))
      (node (ref "U12") (pin "1") (pinfunction "IN+_1") (pintype "input"))
      (node (ref "U12") (pin "2") (pinfunction "IN+_2") (pintype "input"))
    )
    (net (code "94") (name "/VOUT8~{}") (class "Default")
      (node (ref "R9") (pin "2") (pinfunction "2_2") (pintype "passive"))
      (node (ref "U$5") (pin "5") (pinfunction "P$5_5") (pintype "bidirectional"))
      (node (ref "U12") (pin "3") (pinfunction "IN-_3") (pintype "input"))
      (node (ref "U12") (pin "4") (pinfunction "IN-_4") (pintype "input"))
    )
    (net (code "95") (name "/VOUT9") (class "Default")
      (node (ref "C14") (pin "2") (pinfunction "2_2") (pintype "passive"))
      (node (ref "K9") (pin "14.1") (pinfunction "14_14.1") (pintype "passive"))
      (node (ref "K9") (pin "14.2") (pinfunction "14_14.2") (pintype "passive"))
      (node (ref "U13") (pin "1") (pinfunction "IN+_1") (pintype "input"))
      (node (ref "U13") (pin "2") (pinfunction "IN+_2") (pintype "input"))
    )
    (net (code "96") (name "/VOUT9~{}") (class "Default")
      (node (ref "R10") (pin "2") (pinfunction "2_2") (pintype "passive"))
      (node (ref "U$6") (pin "2") (pinfunction "P$2_2") (pintype "bidirectional"))
      (node (ref "U13") (pin "3") (pinfunction "IN-_3") (pintype "input"))
      (node (ref "U13") (pin "4") (pinfunction "IN-_4") (pintype "input"))
    )
    (net (code "97") (name "/VOUT10") (class "Default")
      (node (ref "C15") (pin "2") (pinfunction "2_2") (pintype "passive"))
      (node (ref "K10") (pin "14.1") (pinfunction "14_14.1") (pintype "passive"))
      (node (ref "K10") (pin "14.2") (pinfunction "14_14.2") (pintype "passive"))
      (node (ref "U14") (pin "1") (pinfunction "IN+_1") (pintype "input"))
      (node (ref "U14") (pin "2") (pinfunction "IN+_2") (pintype "input"))
    )
    (net (code "98") (name "/VOUT10~{}") (class "Default")
      (node (ref "R11") (pin "2") (pinfunction "2_2") (pintype "passive"))
      (node (ref "U$6") (pin "4") (pinfunction "P$4_4") (pintype "bidirectional"))
      (node (ref "U14") (pin "3") (pinfunction "IN-_3") (pintype "input"))
      (node (ref "U14") (pin "4") (pinfunction "IN-_4") (pintype "input"))
    )
    (net (code "99") (name "/VS-NC") (class "Default")
      (node (ref "J5") (pin "1") (pinfunction "1_1") (pintype "passive"))
    )
    (net (code "100") (name "/VS1") (class "Default")
      (node (ref "K1") (pin "11.1") (pinfunction "11_11.1") (pintype "passive"))
      (node (ref "K1") (pin "11.2") (pinfunction "11_11.2") (pintype "passive"))
      (node (ref "U$1") (pin "1") (pinfunction "P$1_1") (pintype "bidirectional"))
    )
    (net (code "101") (name "/VS2") (class "Default")
      (node (ref "K2") (pin "11.1") (pinfunction "11_11.1") (pintype "passive"))
      (node (ref "K2") (pin "11.2") (pinfunction "11_11.2") (pintype "passive"))
      (node (ref "U$1") (pin "2") (pinfunction "P$2_2") (pintype "bidirectional"))
    )
    (net (code "102") (name "/VS3") (class "Default")
      (node (ref "K3") (pin "11.1") (pinfunction "11_11.1") (pintype "passive"))
      (node (ref "K3") (pin "11.2") (pinfunction "11_11.2") (pintype "passive"))
      (node (ref "U$1") (pin "3") (pinfunction "P$3_3") (pintype "bidirectional"))
    )
    (net (code "103") (name "/VS4") (class "Default")
      (node (ref "K4") (pin "11.1") (pinfunction "11_11.1") (pintype "passive"))
      (node (ref "K4") (pin "11.2") (pinfunction "11_11.2") (pintype "passive"))
      (node (ref "U$1") (pin "4") (pinfunction "P$4_4") (pintype "bidirectional"))
    )
    (net (code "104") (name "/VS5") (class "Default")
      (node (ref "K5") (pin "11.1") (pinfunction "11_11.1") (pintype "passive"))
      (node (ref "K5") (pin "11.2") (pinfunction "11_11.2") (pintype "passive"))
      (node (ref "U$1") (pin "5") (pinfunction "P$5_5") (pintype "bidirectional"))
    )
    (net (code "105") (name "/VS6") (class "Default")
      (node (ref "K6") (pin "11.1") (pinfunction "11_11.1") (pintype "passive"))
      (node (ref "K6") (pin "11.2") (pinfunction "11_11.2") (pintype "passive"))
      (node (ref "U$2") (pin "1") (pinfunction "P$1_1") (pintype "bidirectional"))
    )
    (net (code "106") (name "/VS7") (class "Default")
      (node (ref "K7") (pin "11.1") (pinfunction "11_11.1") (pintype "passive"))
      (node (ref "K7") (pin "11.2") (pinfunction "11_11.2") (pintype "passive"))
      (node (ref "U$2") (pin "2") (pinfunction "P$2_2") (pintype "bidirectional"))
    )
    (net (code "107") (name "/VS8") (class "Default")
      (node (ref "K8") (pin "11.1") (pinfunction "11_11.1") (pintype "passive"))
      (node (ref "K8") (pin "11.2") (pinfunction "11_11.2") (pintype "passive"))
      (node (ref "U$2") (pin "3") (pinfunction "P$3_3") (pintype "bidirectional"))
    )
    (net (code "108") (name "/VS9") (class "Default")
      (node (ref "K9") (pin "11.1") (pinfunction "11_11.1") (pintype "passive"))
      (node (ref "K9") (pin "11.2") (pinfunction "11_11.2") (pintype "passive"))
      (node (ref "U$2") (pin "4") (pinfunction "P$4_4") (pintype "bidirectional"))
    )
    (net (code "109") (name "/VS10") (class "Default")
      (node (ref "K10") (pin "11.1") (pinfunction "11_11.1") (pintype "passive"))
      (node (ref "K10") (pin "11.2") (pinfunction "11_11.2") (pintype "passive"))
      (node (ref "U$2") (pin "5") (pinfunction "P$5_5") (pintype "bidirectional"))
    )
    (net (code "110") (name "/VS_NC") (class "Default")
      (node (ref "J3") (pin "27") (pinfunction "27_27") (pintype "passive"))
    )
    (net (code "111") (name "GND") (class "Default")
      (node (ref "J1") (pin "2") (pinfunction "2_2") (pintype "passive"))
      (node (ref "J4") (pin "4") (pinfunction "4_4") (pintype "passive"))
      (node (ref "U1") (pin "8") (pinfunction "E_8") (pintype "input"))
      (node (ref "U3") (pin "8") (pinfunction "E_8") (pintype "input"))
      (node (ref "U4") (pin "8") (pinfunction "E_8") (pintype "input"))
    )
    (net (code "112") (name "ISO") (class "Default")
      (node (ref "C1") (pin "2") (pinfunction "2_2") (pintype "passive"))
      (node (ref "C2") (pin "2") (pinfunction "2_2") (pintype "passive"))
      (node (ref "C3") (pin "2") (pinfunction "2_2") (pintype "passive"))
      (node (ref "C4") (pin "2") (pinfunction "2_2") (pintype "passive"))
      (node (ref "C5") (pin "2") (pinfunction "2_2") (pintype "passive"))
      (node (ref "D1") (pin "A") (pinfunction "A_A") (pintype "passive"))
      (node (ref "R1") (pin "2") (pinfunction "2_2") (pintype "passive"))
      (node (ref "U2") (pin "3") (pinfunction "GND_3") (pintype "passive"))
      (node (ref "U2") (pin "5") (pinfunction "ON/OFF_5") (pintype "input"))
      (node (ref "U2") (pin "6") (pinfunction "GND_6") (pintype "passive"))
    )
    (net (code "113") (name "Net-(I$1-1)") (class "Default")
      (node (ref "D1") (pin "C") (pinfunction "C_C") (pintype "passive"))
      (node (ref "I$1") (pin "P$1") (pinfunction "1_P$1") (pintype "passive"))
      (node (ref "U2") (pin "2") (pinfunction "OUT_2") (pintype "output"))
    )
    (net (code "114") (name "Net-(K1-12-Pad12.1)") (class "Default")
      (node (ref "K1") (pin "12.1") (pinfunction "12_12.1") (pintype "passive"))
      (node (ref "K1") (pin "12.2") (pinfunction "12_12.2") (pintype "passive"))
    )
    (net (code "115") (name "Net-(K2-12-Pad12.1)") (class "Default")
      (node (ref "K2") (pin "12.1") (pinfunction "12_12.1") (pintype "passive"))
      (node (ref "K2") (pin "12.2") (pinfunction "12_12.2") (pintype "passive"))
    )
    (net (code "116") (name "Net-(K3-12-Pad12.1)") (class "Default")
      (node (ref "K3") (pin "12.1") (pinfunction "12_12.1") (pintype "passive"))
      (node (ref "K3") (pin "12.2") (pinfunction "12_12.2") (pintype "passive"))
    )
    (net (code "117") (name "Net-(K4-12-Pad12.1)") (class "Default")
      (node (ref "K4") (pin "12.1") (pinfunction "12_12.1") (pintype "passive"))
      (node (ref "K4") (pin "12.2") (pinfunction "12_12.2") (pintype "passive"))
    )
    (net (code "118") (name "Net-(K5-12-Pad12.1)") (class "Default")
      (node (ref "K5") (pin "12.1") (pinfunction "12_12.1") (pintype "passive"))
      (node (ref "K5") (pin "12.2") (pinfunction "12_12.2") (pintype "passive"))
    )
    (net (code "119") (name "Net-(K6-12-Pad12.1)") (class "Default")
      (node (ref "K6") (pin "12.1") (pinfunction "12_12.1") (pintype "passive"))
      (node (ref "K6") (pin "12.2") (pinfunction "12_12.2") (pintype "passive"))
    )
    (net (code "120") (name "Net-(K7-12-Pad12.1)") (class "Default")
      (node (ref "K7") (pin "12.1") (pinfunction "12_12.1") (pintype "passive"))
      (node (ref "K7") (pin "12.2") (pinfunction "12_12.2") (pintype "passive"))
    )
    (net (code "121") (name "Net-(K8-12-Pad12.1)") (class "Default")
      (node (ref "K8") (pin "12.1") (pinfunction "12_12.1") (pintype "passive"))
      (node (ref "K8") (pin "12.2") (pinfunction "12_12.2") (pintype "passive"))
    )
    (net (code "122") (name "Net-(K9-12-Pad12.1)") (class "Default")
      (node (ref "K9") (pin "12.1") (pinfunction "12_12.1") (pintype "passive"))
      (node (ref "K9") (pin "12.2") (pinfunction "12_12.2") (pintype "passive"))
    )
    (net (code "123") (name "Net-(K10-12-Pad12.1)") (class "Default")
      (node (ref "K10") (pin "12.1") (pinfunction "12_12.1") (pintype "passive"))
      (node (ref "K10") (pin "12.2") (pinfunction "12_12.2") (pintype "passive"))
    )
    (net (code "124") (name "Net-(K11-12-Pad12.1)") (class "Default")
      (node (ref "K11") (pin "12.1") (pinfunction "12_12.1") (pintype "passive"))
      (node (ref "K11") (pin "12.2") (pinfunction "12_12.2") (pintype "passive"))
    )
    (net (code "125") (name "Net-(RN3D-2)") (class "Default")
      (node (ref "RN3") (pin "5") (pinfunction "2_5") (pintype "passive"))
      (node (ref "U1") (pin "9") (pinfunction "COM_9") (pintype "output"))
    )
    (net (code "126") (name "Net-(RN4D-2)") (class "Default")
      (node (ref "RN4") (pin "5") (pinfunction "2_5") (pintype "passive"))
      (node (ref "U3") (pin "9") (pinfunction "COM_9") (pintype "output"))
    )
    (net (code "127") (name "Net-(RN5D-2)") (class "Default")
      (node (ref "RN5") (pin "5") (pinfunction "2_5") (pintype "passive"))
      (node (ref "U4") (pin "9") (pinfunction "COM_9") (pintype "output"))
    )
    (net (code "128") (name "RTN") (class "Default")
      (node (ref "C10") (pin "1") (pinfunction "1_1") (pintype "passive"))
      (node (ref "C11") (pin "1") (pinfunction "1_1") (pintype "passive"))
      (node (ref "C12") (pin "1") (pinfunction "1_1") (pintype "passive"))
      (node (ref "C13") (pin "1") (pinfunction "1_1") (pintype "passive"))
      (node (ref "C14") (pin "1") (pinfunction "1_1") (pintype "passive"))
      (node (ref "C15") (pin "1") (pinfunction "1_1") (pintype "passive"))
      (node (ref "C17") (pin "1") (pinfunction "1_1") (pintype "passive"))
      (node (ref "C6") (pin "1") (pinfunction "1_1") (pintype "passive"))
      (node (ref "C7") (pin "1") (pinfunction "1_1") (pintype "passive"))
      (node (ref "C8") (pin "1") (pinfunction "1_1") (pintype "passive"))
      (node (ref "C9") (pin "1") (pinfunction "1_1") (pintype "passive"))
      (node (ref "J1") (pin "3") (pinfunction "3_3") (pintype "passive"))
      (node (ref "J3") (pin "1") (pinfunction "1_1") (pintype "passive"))
      (node (ref "J3") (pin "10") (pinfunction "10_10") (pintype "passive"))
      (node (ref "J3") (pin "19") (pinfunction "19_19") (pintype "passive"))
      (node (ref "J3") (pin "30") (pinfunction "30_30") (pintype "passive"))
      (node (ref "J3") (pin "8") (pinfunction "8_8") (pintype "passive"))
      (node (ref "J4") (pin "5") (pinfunction "5_5") (pintype "passive"))
      (node (ref "J4") (pin "6") (pinfunction "6_6") (pintype "passive"))
      (node (ref "J5") (pin "11") (pinfunction "11_11") (pintype "passive"))
      (node (ref "J5") (pin "8") (pinfunction "8_8") (pintype "passive"))
      (node (ref "R1") (pin "1") (pinfunction "1_1") (pintype "passive"))
      (node (ref "U$3") (pin "2") (pinfunction "P$2_2") (pintype "bidirectional"))
      (node (ref "U$3") (pin "4") (pinfunction "P$4_4") (pintype "bidirectional"))
      (node (ref "U$4") (pin "1") (pinfunction "P$1_1") (pintype "bidirectional"))
      (node (ref "U$4") (pin "3") (pinfunction "P$3_3") (pintype "bidirectional"))
      (node (ref "U$4") (pin "5") (pinfunction "P$5_5") (pintype "bidirectional"))
      (node (ref "U$5") (pin "2") (pinfunction "P$2_2") (pintype "bidirectional"))
      (node (ref "U$5") (pin "4") (pinfunction "P$4_4") (pintype "bidirectional"))
      (node (ref "U$6") (pin "1") (pinfunction "P$1_1") (pintype "bidirectional"))
      (node (ref "U$6") (pin "3") (pinfunction "P$3_3") (pintype "bidirectional"))
      (node (ref "U$6") (pin "5") (pinfunction "P$5_5") (pintype "bidirectional"))
      (node (ref "U10") (pin "5") (pinfunction "GND_5") (pintype "power_in"))
      (node (ref "U11") (pin "5") (pinfunction "GND_5") (pintype "power_in"))
      (node (ref "U12") (pin "5") (pinfunction "GND_5") (pintype "power_in"))
      (node (ref "U13") (pin "5") (pinfunction "GND_5") (pintype "power_in"))
      (node (ref "U14") (pin "5") (pinfunction "GND_5") (pintype "power_in"))
      (node (ref "U5") (pin "5") (pinfunction "GND_5") (pintype "power_in"))
      (node (ref "U6") (pin "5") (pinfunction "GND_5") (pintype "power_in"))
      (node (ref "U7") (pin "5") (pinfunction "GND_5") (pintype "power_in"))
      (node (ref "U8") (pin "5") (pinfunction "GND_5") (pintype "power_in"))
      (node (ref "U9") (pin "5") (pinfunction "GND_5") (pintype "power_in"))
    )
    (net (code "129") (name "VCC") (class "Default")
      (node (ref "C2") (pin "1") (pinfunction "1_1") (pintype "passive"))
      (node (ref "C3") (pin "1") (pinfunction "1_1") (pintype "passive"))
      (node (ref "C4") (pin "1") (pinfunction "1_1") (pintype "passive"))
      (node (ref "C5") (pin "1") (pinfunction "1_1") (pintype "passive"))
      (node (ref "I$1") (pin "P$2") (pinfunction "2_P$2") (pintype "passive"))
      (node (ref "J4") (pin "2") (pinfunction "2_2") (pintype "passive"))
      (node (ref "K11") (pin "11.1") (pinfunction "11_11.1") (pintype "passive"))
      (node (ref "K11") (pin "11.2") (pinfunction "11_11.2") (pintype "passive"))
      (node (ref "U10") (pin "8") (pinfunction "VS_8") (pintype "power_in"))
      (node (ref "U11") (pin "8") (pinfunction "VS_8") (pintype "power_in"))
      (node (ref "U12") (pin "8") (pinfunction "VS_8") (pintype "power_in"))
      (node (ref "U13") (pin "8") (pinfunction "VS_8") (pintype "power_in"))
      (node (ref "U14") (pin "8") (pinfunction "VS_8") (pintype "power_in"))
      (node (ref "U2") (pin "4") (pinfunction "FB_4") (pintype "output"))
      (node (ref "U5") (pin "8") (pinfunction "VS_8") (pintype "power_in"))
      (node (ref "U6") (pin "8") (pinfunction "VS_8") (pintype "power_in"))
      (node (ref "U7") (pin "8") (pinfunction "VS_8") (pintype "power_in"))
      (node (ref "U8") (pin "8") (pinfunction "VS_8") (pintype "power_in"))
      (node (ref "U9") (pin "8") (pinfunction "VS_8") (pintype "power_in"))
    )
    (net (code "130") (name "unconnected-(C1-Pad1)") (class "Default")
      (node (ref "C1") (pin "1") (pinfunction "1_1") (pintype "passive"))
    )
    (net (code "131") (name "unconnected-(J2-Pad11)") (class "Default")
      (node (ref "J2") (pin "11") (pinfunction "11_11") (pintype "passive"))
    )
    (net (code "132") (name "unconnected-(J2-Pad12)") (class "Default")
      (node (ref "J2") (pin "12") (pinfunction "12_12") (pintype "passive"))
    )
    (net (code "133") (name "unconnected-(J2-Pad14)") (class "Default")
      (node (ref "J2") (pin "14") (pinfunction "14_14") (pintype "passive"))
    )
    (net (code "134") (name "unconnected-(K1-PadA3)") (class "Default")
      (node (ref "K1") (pin "A3") (pinfunction "A3_A3") (pintype "passive"))
    )
    (net (code "135") (name "unconnected-(K2-PadA3)") (class "Default")
      (node (ref "K2") (pin "A3") (pinfunction "A3_A3") (pintype "passive"))
    )
    (net (code "136") (name "unconnected-(K3-PadA3)") (class "Default")
      (node (ref "K3") (pin "A3") (pinfunction "A3_A3") (pintype "passive"))
    )
    (net (code "137") (name "unconnected-(K4-PadA3)") (class "Default")
      (node (ref "K4") (pin "A3") (pinfunction "A3_A3") (pintype "passive"))
    )
    (net (code "138") (name "unconnected-(K5-PadA3)") (class "Default")
      (node (ref "K5") (pin "A3") (pinfunction "A3_A3") (pintype "passive"))
    )
    (net (code "139") (name "unconnected-(K6-PadA3)") (class "Default")
      (node (ref "K6") (pin "A3") (pinfunction "A3_A3") (pintype "passive"))
    )
    (net (code "140") (name "unconnected-(K7-PadA3)") (class "Default")
      (node (ref "K7") (pin "A3") (pinfunction "A3_A3") (pintype "passive"))
    )
    (net (code "141") (name "unconnected-(K8-PadA3)") (class "Default")
      (node (ref "K8") (pin "A3") (pinfunction "A3_A3") (pintype "passive"))
    )
    (net (code "142") (name "unconnected-(K9-PadA3)") (class "Default")
      (node (ref "K9") (pin "A3") (pinfunction "A3_A3") (pintype "passive"))
    )
    (net (code "143") (name "unconnected-(K10-PadA3)") (class "Default")
      (node (ref "K10") (pin "A3") (pinfunction "A3_A3") (pintype "passive"))
    )
    (net (code "144") (name "unconnected-(K11-PadA3)") (class "Default")
      (node (ref "K11") (pin "A3") (pinfunction "A3_A3") (pintype "passive"))
    )
    (net (code "145") (name "unconnected-(RN5C-2-Pad6)") (class "Default")
      (node (ref "RN5") (pin "6") (pinfunction "2_6") (pintype "passive"))
    )
    (net (code "146") (name "unconnected-(U4-7B-Pad7)") (class "Default")
      (node (ref "U4") (pin "7") (pinfunction "7B_7") (pintype "input"))
    )
    (net (code "147") (name "unconnected-(U4-7C-Pad10)") (class "Default")
      (node (ref "U4") (pin "10") (pinfunction "7C_10") (pintype "output"))
    )
    (net (code "148") (name "unconnected-(U5-NC-Pad6)") (class "Default")
      (node (ref "U5") (pin "6") (pinfunction "NC_6") (pintype "no_connect"))
    )
    (net (code "149") (name "unconnected-(U6-NC-Pad6)") (class "Default")
      (node (ref "U6") (pin "6") (pinfunction "NC_6") (pintype "no_connect"))
    )
    (net (code "150") (name "unconnected-(U7-NC-Pad6)") (class "Default")
      (node (ref "U7") (pin "6") (pinfunction "NC_6") (pintype "no_connect"))
    )
    (net (code "151") (name "unconnected-(U8-NC-Pad6)") (class "Default")
      (node (ref "U8") (pin "6") (pinfunction "NC_6") (pintype "no_connect"))
    )
    (net (code "152") (name "unconnected-(U9-NC-Pad6)") (class "Default")
      (node (ref "U9") (pin "6") (pinfunction "NC_6") (pintype "no_connect"))
    )
    (net (code "153") (name "unconnected-(U10-NC-Pad6)") (class "Default")
      (node (ref "U10") (pin "6") (pinfunction "NC_6") (pintype "no_connect"))
    )
    (net (code "154") (name "unconnected-(U11-NC-Pad6)") (class "Default")
      (node (ref "U11") (pin "6") (pinfunction "NC_6") (pintype "no_connect"))
    )
    (net (code "155") (name "unconnected-(U12-NC-Pad6)") (class "Default")
      (node (ref "U12") (pin "6") (pinfunction "NC_6") (pintype "no_connect"))
    )
    (net (code "156") (name "unconnected-(U13-NC-Pad6)") (class "Default")
      (node (ref "U13") (pin "6") (pinfunction "NC_6") (pintype "no_connect"))
    )
    (net (code "157") (name "unconnected-(U14-NC-Pad6)") (class "Default")
      (node (ref "U14") (pin "6") (pinfunction "NC_6") (pintype "no_connect"))
    )
  )
)
